# Quadcopter.net
KiCad netlist of a schematic drawn in EAGLE
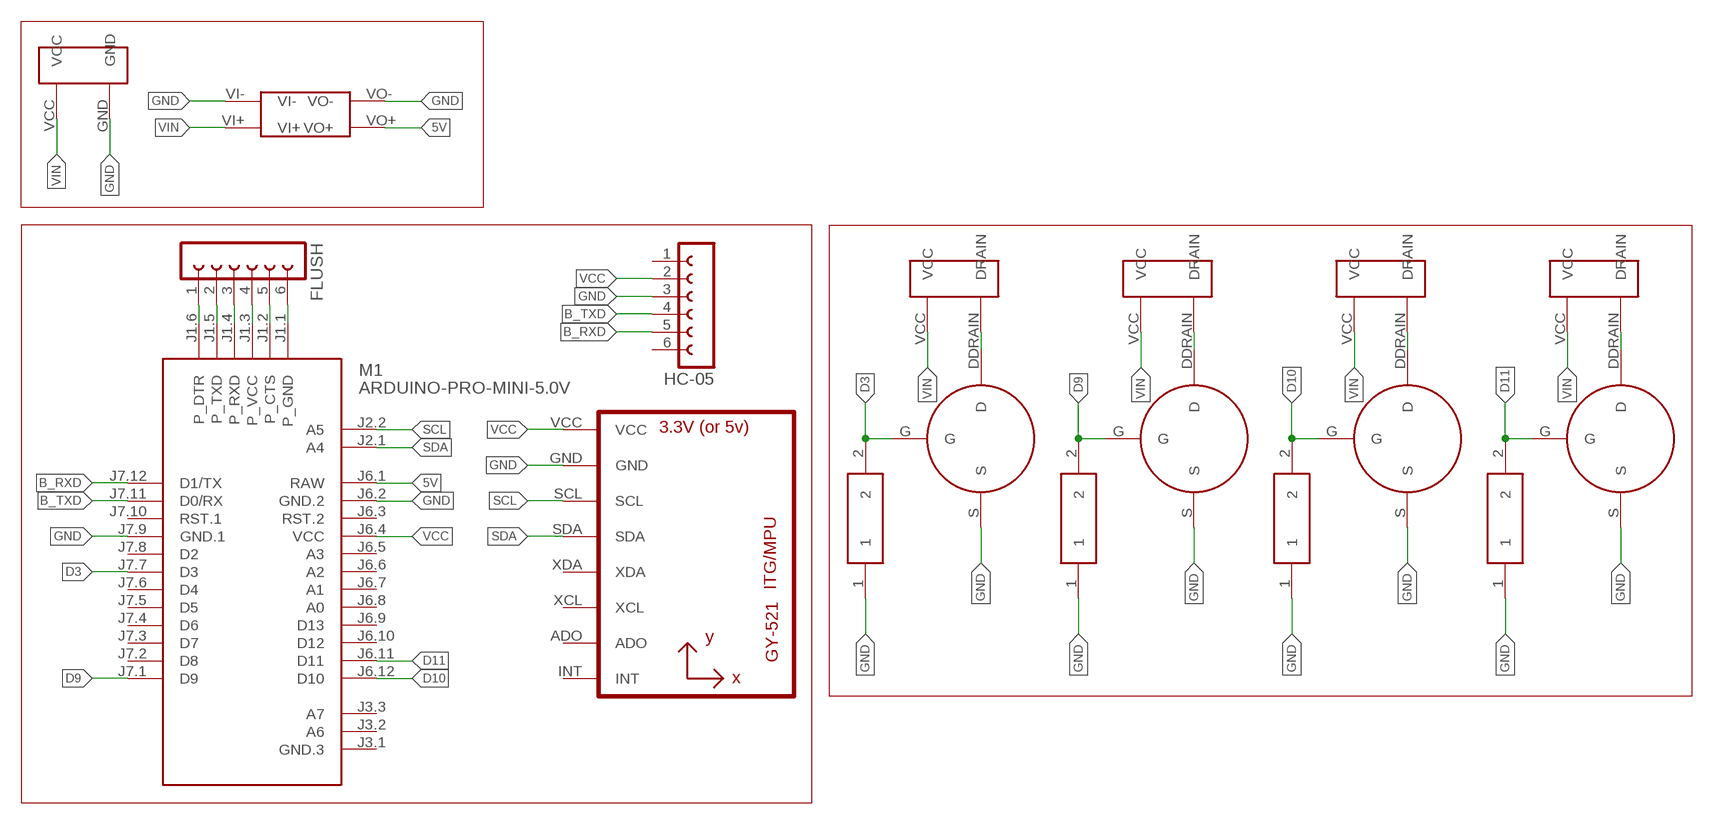
[diagram p0: schematic, sheet 1]

(export (version "E")
  (design (tool "Eeschema 10.0.6"))
  (components
    (comp (ref "FLUSH")
      (value "FE06-1")
      (footprint "eagle-import:FE06")
      (libsource (lib "eagle-import") (part "FE06-1"))
    )
    (comp (ref "HC-05")
      (value "FE06-1")
      (footprint "eagle-import:FE06")
      (libsource (lib "eagle-import") (part "FE06-1"))
    )
    (comp (ref "M1")
      (value "ARDUINO-PRO-MINI-5.0V")
      (footprint "eagle-import:ARDUINO-PRO-MINI")
      (libsource (lib "eagle-import") (part "ARDUINO-PRO-MINI-5.0V"))
    )
    (comp (ref "U$1")
      (value "SI2306")
      (footprint "eagle-import:SI2306")
      (libsource (lib "eagle-import") (part "SI2306"))
    )
    (comp (ref "U$2")
      (value "1206_RESISTOR")
      (footprint "eagle-import:1206_RESISTOR")
      (libsource (lib "eagle-import") (part "1206_RESISTOR"))
    )
    (comp (ref "U$3")
      (value "5V_TRANSFORMER")
      (footprint "eagle-import:5V_TRANSFORMER")
      (libsource (lib "eagle-import") (part "5V_TRANSFORMER"))
    )
    (comp (ref "U$4")
      (value "POWER_MAIN")
      (footprint "eagle-import:POWER_MAIN")
      (libsource (lib "eagle-import") (part "POWER_MAIN"))
    )
    (comp (ref "U$5")
      (value "POWER_MOTOR")
      (footprint "eagle-import:POWER_MOTOR")
      (libsource (lib "eagle-import") (part "POWER_MOTOR"))
    )
    (comp (ref "U$6")
      (value "SI2306")
      (footprint "eagle-import:SI2306")
      (libsource (lib "eagle-import") (part "SI2306"))
    )
    (comp (ref "U$7")
      (value "1206_RESISTOR")
      (footprint "eagle-import:1206_RESISTOR")
      (libsource (lib "eagle-import") (part "1206_RESISTOR"))
    )
    (comp (ref "U$8")
      (value "POWER_MOTOR")
      (footprint "eagle-import:POWER_MOTOR")
      (libsource (lib "eagle-import") (part "POWER_MOTOR"))
    )
    (comp (ref "U$9")
      (value "SI2306")
      (footprint "eagle-import:SI2306")
      (libsource (lib "eagle-import") (part "SI2306"))
    )
    (comp (ref "U$10")
      (value "1206_RESISTOR")
      (footprint "eagle-import:1206_RESISTOR")
      (libsource (lib "eagle-import") (part "1206_RESISTOR"))
    )
    (comp (ref "U$11")
      (value "POWER_MOTOR")
      (footprint "eagle-import:POWER_MOTOR")
      (libsource (lib "eagle-import") (part "POWER_MOTOR"))
    )
    (comp (ref "U$12")
      (value "SI2306")
      (footprint "eagle-import:SI2306")
      (libsource (lib "eagle-import") (part "SI2306"))
    )
    (comp (ref "U$13")
      (value "1206_RESISTOR")
      (footprint "eagle-import:1206_RESISTOR")
      (libsource (lib "eagle-import") (part "1206_RESISTOR"))
    )
    (comp (ref "U$14")
      (value "POWER_MOTOR")
      (footprint "eagle-import:POWER_MOTOR")
      (libsource (lib "eagle-import") (part "POWER_MOTOR"))
    )
    (comp (ref "U1")
      (value "GY-521MPU6050")
      (footprint "eagle-import:GY-521")
      (libsource (lib "eagle-import") (part "GY-521MPU6050"))
    )
  )
  (nets
    (net (code "1") (name "5V") (class "Default")
      (node (ref "M1") (pin "J6.1") (pinfunction "RAW_J6.1") (pintype "power_in"))
      (node (ref "U$3") (pin "VO+") (pinfunction "VO+_VO+") (pintype "bidirectional"))
    )
    (net (code "2") (name "B_RXD") (class "Default")
      (node (ref "HC-05") (pin "5") (pinfunction "5_5") (pintype "passive"))
      (node (ref "M1") (pin "J7.12") (pinfunction "D1/TX_J7.12") (pintype "bidirectional"))
    )
    (net (code "3") (name "B_TXD") (class "Default")
      (node (ref "HC-05") (pin "4") (pinfunction "4_4") (pintype "passive"))
      (node (ref "M1") (pin "J7.11") (pinfunction "D0/RX_J7.11") (pintype "bidirectional"))
    )
    (net (code "4") (name "D3") (class "Default")
      (node (ref "M1") (pin "J7.7") (pinfunction "D3_J7.7") (pintype "bidirectional"))
      (node (ref "U$1") (pin "G") (pinfunction "G_G") (pintype "bidirectional"))
      (node (ref "U$2") (pin "2") (pinfunction "2_2") (pintype "bidirectional"))
    )
    (net (code "5") (name "D9") (class "Default")
      (node (ref "M1") (pin "J7.1") (pinfunction "D9_J7.1") (pintype "bidirectional"))
      (node (ref "U$6") (pin "G") (pinfunction "G_G") (pintype "bidirectional"))
      (node (ref "U$7") (pin "2") (pinfunction "2_2") (pintype "bidirectional"))
    )
    (net (code "6") (name "D10") (class "Default")
      (node (ref "M1") (pin "J6.12") (pinfunction "D10_J6.12") (pintype "bidirectional"))
      (node (ref "U$10") (pin "2") (pinfunction "2_2") (pintype "bidirectional"))
      (node (ref "U$9") (pin "G") (pinfunction "G_G") (pintype "bidirectional"))
    )
    (net (code "7") (name "D11") (class "Default")
      (node (ref "M1") (pin "J6.11") (pinfunction "D11_J6.11") (pintype "bidirectional"))
      (node (ref "U$12") (pin "G") (pinfunction "G_G") (pintype "bidirectional"))
      (node (ref "U$13") (pin "2") (pinfunction "2_2") (pintype "bidirectional"))
    )
    (net (code "8") (name "GND") (class "Default")
      (node (ref "HC-05") (pin "3") (pinfunction "3_3") (pintype "passive"))
      (node (ref "M1") (pin "J6.2") (pinfunction "GND.2_J6.2") (pintype "power_in"))
      (node (ref "M1") (pin "J7.9") (pinfunction "GND.1_J7.9") (pintype "power_in"))
      (node (ref "U$1") (pin "S") (pinfunction "S_S") (pintype "bidirectional"))
      (node (ref "U$10") (pin "1") (pinfunction "1_1") (pintype "bidirectional"))
      (node (ref "U$12") (pin "S") (pinfunction "S_S") (pintype "bidirectional"))
      (node (ref "U$13") (pin "1") (pinfunction "1_1") (pintype "bidirectional"))
      (node (ref "U$2") (pin "1") (pinfunction "1_1") (pintype "bidirectional"))
      (node (ref "U$3") (pin "VI-") (pinfunction "VI-_VI-") (pintype "bidirectional"))
      (node (ref "U$3") (pin "VO-") (pinfunction "VO-_VO-") (pintype "bidirectional"))
      (node (ref "U$4") (pin "GND") (pinfunction "GND_GND") (pintype "bidirectional"))
      (node (ref "U$6") (pin "S") (pinfunction "S_S") (pintype "bidirectional"))
      (node (ref "U$7") (pin "1") (pinfunction "1_1") (pintype "bidirectional"))
      (node (ref "U$9") (pin "S") (pinfunction "S_S") (pintype "bidirectional"))
      (node (ref "U1") (pin "GND") (pinfunction "GND_GND") (pintype "bidirectional"))
    )
    (net (code "9") (name "Net-(M1-P_CTS)") (class "Default")
      (node (ref "FLUSH") (pin "5") (pinfunction "5_5") (pintype "passive"))
      (node (ref "M1") (pin "J1.2") (pinfunction "P_CTS_J1.2") (pintype "bidirectional"))
    )
    (net (code "10") (name "Net-(M1-P_DTR)") (class "Default")
      (node (ref "FLUSH") (pin "1") (pinfunction "1_1") (pintype "passive"))
      (node (ref "M1") (pin "J1.6") (pinfunction "P_DTR_J1.6") (pintype "bidirectional"))
    )
    (net (code "11") (name "Net-(M1-P_GND)") (class "Default")
      (node (ref "FLUSH") (pin "6") (pinfunction "6_6") (pintype "passive"))
      (node (ref "M1") (pin "J1.1") (pinfunction "P_GND_J1.1") (pintype "bidirectional"))
    )
    (net (code "12") (name "Net-(M1-P_RXD)") (class "Default")
      (node (ref "FLUSH") (pin "3") (pinfunction "3_3") (pintype "passive"))
      (node (ref "M1") (pin "J1.4") (pinfunction "P_RXD_J1.4") (pintype "bidirectional"))
    )
    (net (code "13") (name "Net-(M1-P_TXD)") (class "Default")
      (node (ref "FLUSH") (pin "2") (pinfunction "2_2") (pintype "passive"))
      (node (ref "M1") (pin "J1.5") (pinfunction "P_TXD_J1.5") (pintype "bidirectional"))
    )
    (net (code "14") (name "Net-(M1-P_VCC)") (class "Default")
      (node (ref "FLUSH") (pin "4") (pinfunction "4_4") (pintype "passive"))
      (node (ref "M1") (pin "J1.3") (pinfunction "P_VCC_J1.3") (pintype "bidirectional"))
    )
    (net (code "15") (name "Net-(U$1-PadD)") (class "Default")
      (node (ref "U$1") (pin "D") (pinfunction "D_D") (pintype "bidirectional"))
      (node (ref "U$5") (pin "DRAIN") (pinfunction "DRAIN_DRAIN") (pintype "bidirectional"))
    )
    (net (code "16") (name "Net-(U$6-PadD)") (class "Default")
      (node (ref "U$6") (pin "D") (pinfunction "D_D") (pintype "bidirectional"))
      (node (ref "U$8") (pin "DRAIN") (pinfunction "DRAIN_DRAIN") (pintype "bidirectional"))
    )
    (net (code "17") (name "Net-(U$11-PadDRAIN)") (class "Default")
      (node (ref "U$11") (pin "DRAIN") (pinfunction "DRAIN_DRAIN") (pintype "bidirectional"))
      (node (ref "U$9") (pin "D") (pinfunction "D_D") (pintype "bidirectional"))
    )
    (net (code "18") (name "Net-(U$12-PadD)") (class "Default")
      (node (ref "U$12") (pin "D") (pinfunction "D_D") (pintype "bidirectional"))
      (node (ref "U$14") (pin "DRAIN") (pinfunction "DRAIN_DRAIN") (pintype "bidirectional"))
    )
    (net (code "19") (name "SCL") (class "Default")
      (node (ref "M1") (pin "J2.2") (pinfunction "A5_J2.2") (pintype "bidirectional"))
      (node (ref "U1") (pin "SCL") (pinfunction "SCL_SCL") (pintype "bidirectional"))
    )
    (net (code "20") (name "SDA") (class "Default")
      (node (ref "M1") (pin "J2.1") (pinfunction "A4_J2.1") (pintype "bidirectional"))
      (node (ref "U1") (pin "SDA") (pinfunction "SDA_SDA") (pintype "bidirectional"))
    )
    (net (code "21") (name "VCC") (class "Default")
      (node (ref "HC-05") (pin "2") (pinfunction "2_2") (pintype "passive"))
      (node (ref "M1") (pin "J6.4") (pinfunction "VCC_J6.4") (pintype "power_in"))
      (node (ref "U1") (pin "VCC") (pinfunction "VCC_VCC") (pintype "bidirectional"))
    )
    (net (code "22") (name "VIN") (class "Default")
      (node (ref "U$11") (pin "VCC") (pinfunction "VCC_VCC") (pintype "bidirectional"))
      (node (ref "U$14") (pin "VCC") (pinfunction "VCC_VCC") (pintype "bidirectional"))
      (node (ref "U$3") (pin "VI+") (pinfunction "VI+_VI+") (pintype "bidirectional"))
      (node (ref "U$4") (pin "VCC") (pinfunction "VCC_VCC") (pintype "bidirectional"))
      (node (ref "U$5") (pin "VCC") (pinfunction "VCC_VCC") (pintype "bidirectional"))
      (node (ref "U$8") (pin "VCC") (pinfunction "VCC_VCC") (pintype "bidirectional"))
    )
    (net (code "23") (name "unconnected-(HC-05-Pad1)") (class "Default")
      (node (ref "HC-05") (pin "1") (pinfunction "1_1") (pintype "passive"))
    )
    (net (code "24") (name "unconnected-(HC-05-Pad6)") (class "Default")
      (node (ref "HC-05") (pin "6") (pinfunction "6_6") (pintype "passive"))
    )
    (net (code "25") (name "unconnected-(M1-A0-PadJ6.8)") (class "Default")
      (node (ref "M1") (pin "J6.8") (pinfunction "A0_J6.8") (pintype "bidirectional"))
    )
    (net (code "26") (name "unconnected-(M1-A1-PadJ6.7)") (class "Default")
      (node (ref "M1") (pin "J6.7") (pinfunction "A1_J6.7") (pintype "bidirectional"))
    )
    (net (code "27") (name "unconnected-(M1-A2-PadJ6.6)") (class "Default")
      (node (ref "M1") (pin "J6.6") (pinfunction "A2_J6.6") (pintype "bidirectional"))
    )
    (net (code "28") (name "unconnected-(M1-A3-PadJ6.5)") (class "Default")
      (node (ref "M1") (pin "J6.5") (pinfunction "A3_J6.5") (pintype "bidirectional"))
    )
    (net (code "29") (name "unconnected-(M1-A6-PadJ3.2)") (class "Default")
      (node (ref "M1") (pin "J3.2") (pinfunction "A6_J3.2") (pintype "bidirectional"))
    )
    (net (code "30") (name "unconnected-(M1-A7-PadJ3.3)") (class "Default")
      (node (ref "M1") (pin "J3.3") (pinfunction "A7_J3.3") (pintype "bidirectional"))
    )
    (net (code "31") (name "unconnected-(M1-D2-PadJ7.8)") (class "Default")
      (node (ref "M1") (pin "J7.8") (pinfunction "D2_J7.8") (pintype "bidirectional"))
    )
    (net (code "32") (name "unconnected-(M1-D4-PadJ7.6)") (class "Default")
      (node (ref "M1") (pin "J7.6") (pinfunction "D4_J7.6") (pintype "bidirectional"))
    )
    (net (code "33") (name "unconnected-(M1-D5-PadJ7.5)") (class "Default")
      (node (ref "M1") (pin "J7.5") (pinfunction "D5_J7.5") (pintype "bidirectional"))
    )
    (net (code "34") (name "unconnected-(M1-D6-PadJ7.4)") (class "Default")
      (node (ref "M1") (pin "J7.4") (pinfunction "D6_J7.4") (pintype "bidirectional"))
    )
    (net (code "35") (name "unconnected-(M1-D7-PadJ7.3)") (class "Default")
      (node (ref "M1") (pin "J7.3") (pinfunction "D7_J7.3") (pintype "bidirectional"))
    )
    (net (code "36") (name "unconnected-(M1-D8-PadJ7.2)") (class "Default")
      (node (ref "M1") (pin "J7.2") (pinfunction "D8_J7.2") (pintype "bidirectional"))
    )
    (net (code "37") (name "unconnected-(M1-D12-PadJ6.10)") (class "Default")
      (node (ref "M1") (pin "J6.10") (pinfunction "D12_J6.10") (pintype "bidirectional"))
    )
    (net (code "38") (name "unconnected-(M1-D13-PadJ6.9)") (class "Default")
      (node (ref "M1") (pin "J6.9") (pinfunction "D13_J6.9") (pintype "bidirectional"))
    )
    (net (code "39") (name "unconnected-(M1-GND.3-PadJ3.1)") (class "Default")
      (node (ref "M1") (pin "J3.1") (pinfunction "GND.3_J3.1") (pintype "bidirectional"))
    )
    (net (code "40") (name "unconnected-(M1-RST.1-PadJ7.10)") (class "Default")
      (node (ref "M1") (pin "J7.10") (pinfunction "RST.1_J7.10") (pintype "bidirectional"))
    )
    (net (code "41") (name "unconnected-(M1-RST.2-PadJ6.3)") (class "Default")
      (node (ref "M1") (pin "J6.3") (pinfunction "RST.2_J6.3") (pintype "bidirectional"))
    )
    (net (code "42") (name "unconnected-(U1-PadADO)") (class "Default")
      (node (ref "U1") (pin "ADO") (pinfunction "ADO_ADO") (pintype "bidirectional"))
    )
    (net (code "43") (name "unconnected-(U1-PadINT)") (class "Default")
      (node (ref "U1") (pin "INT") (pinfunction "INT_INT") (pintype "bidirectional"))
    )
    (net (code "44") (name "unconnected-(U1-PadXCL)") (class "Default")
      (node (ref "U1") (pin "XCL") (pinfunction "XCL_XCL") (pintype "bidirectional"))
    )
    (net (code "45") (name "unconnected-(U1-PadXDA)") (class "Default")
      (node (ref "U1") (pin "XDA") (pinfunction "XDA_XDA") (pintype "bidirectional"))
    )
  )
)
